# 140810_AriloTX_REV3_0_0_433MHZ_td.net
KiCad netlist of a schematic drawn in EAGLE
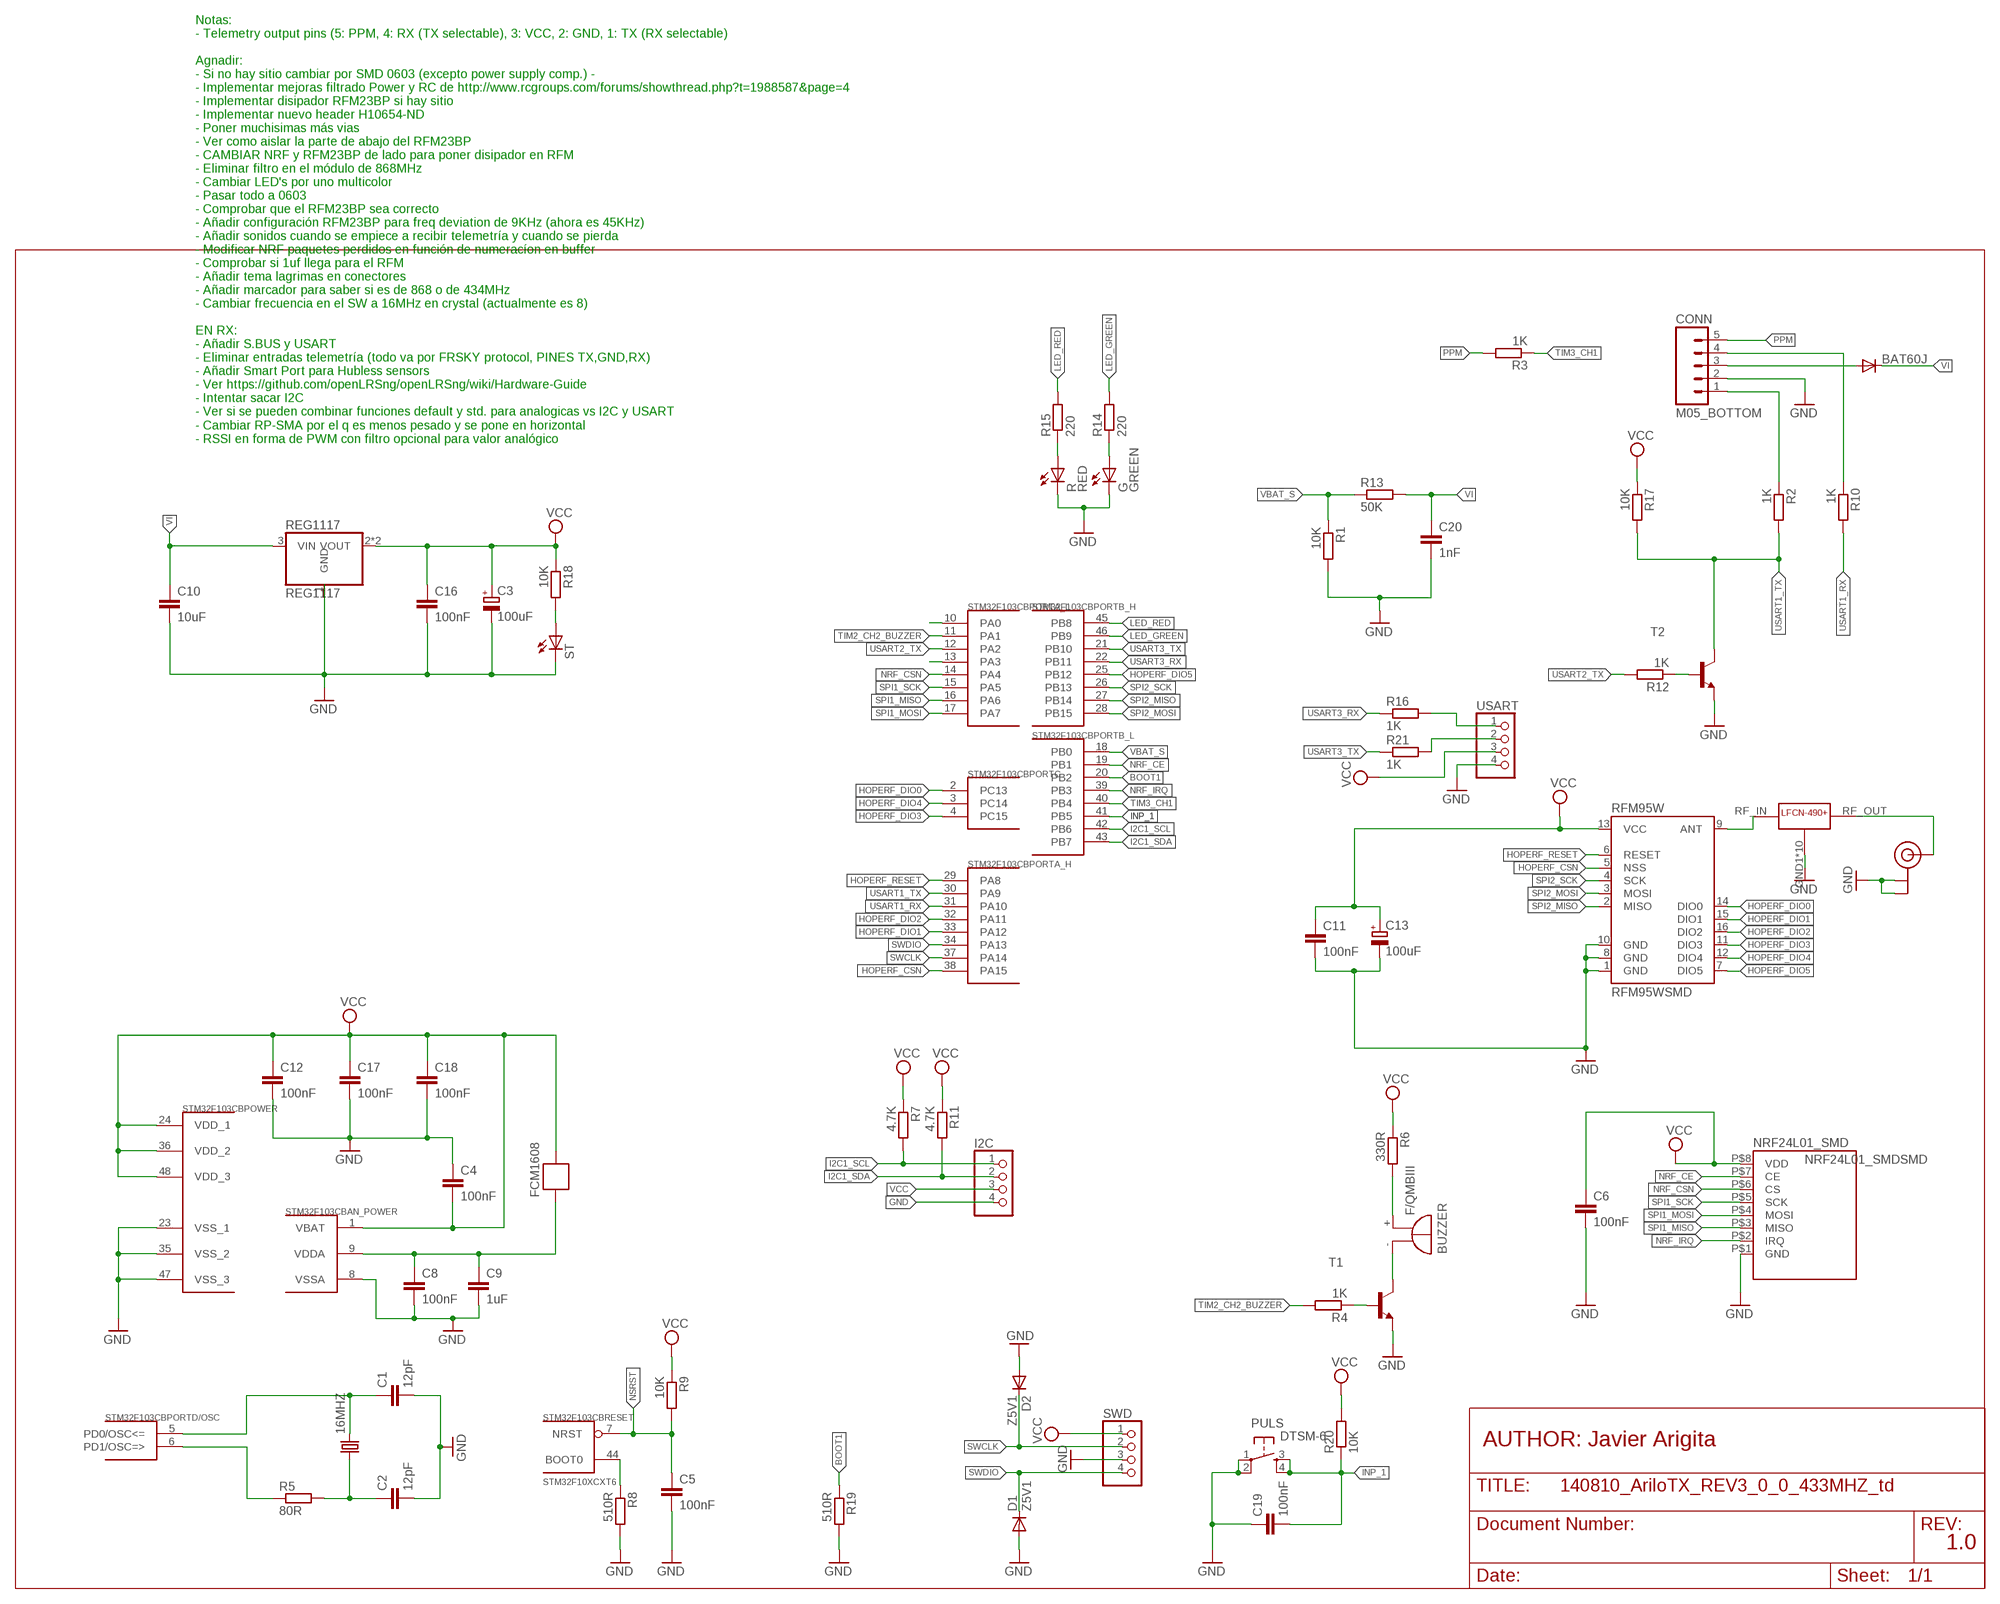
[diagram p0: schematic, sheet 1]

(export (version "E")
  (design (tool "Eeschema 10.0.6"))
  (components
    (comp (ref "16MHZ")
      (value "CRYSTAL5X3")
      (footprint "eagle-import:CRYSTAL-SMD-5X3")
      (libsource (lib "eagle-import") (part "CRYSTAL5X3"))
    )
    (comp (ref "BAT60J")
      (value "DIODE-SOD323-R")
      (footprint "eagle-import:SOD323-R")
      (libsource (lib "eagle-import") (part "DIODE-SOD323-R"))
    )
    (comp (ref "BUZZER")
      (value "F/QMBIII")
      (footprint "eagle-import:F_QMBIII")
      (libsource (lib "eagle-import") (part "F/QMBIII"))
    )
    (comp (ref "C1")
      (value "12pF")
      (footprint "eagle-import:C0603")
      (libsource (lib "eagle-import") (part "C-EUC0603"))
    )
    (comp (ref "C2")
      (value "12pF")
      (footprint "eagle-import:C0603")
      (libsource (lib "eagle-import") (part "C-EUC0603"))
    )
    (comp (ref "C3")
      (value "100uF")
      (footprint "eagle-import:SMC_B")
      (libsource (lib "eagle-import") (part "CPOL-EUSMCB"))
    )
    (comp (ref "C4")
      (value "100nF")
      (footprint "eagle-import:C0603")
      (libsource (lib "eagle-import") (part "C-EUC0603"))
    )
    (comp (ref "C5")
      (value "100nF")
      (footprint "eagle-import:C0603")
      (libsource (lib "eagle-import") (part "C-EUC0603"))
    )
    (comp (ref "C6")
      (value "100nF")
      (footprint "eagle-import:C0603")
      (libsource (lib "eagle-import") (part "C-EUC0603"))
    )
    (comp (ref "C8")
      (value "100nF")
      (footprint "eagle-import:C0603")
      (libsource (lib "eagle-import") (part "C-EUC0603"))
    )
    (comp (ref "C9")
      (value "1uF")
      (footprint "eagle-import:C0603")
      (libsource (lib "eagle-import") (part "C-EUC0603"))
    )
    (comp (ref "C10")
      (value "10uF")
      (footprint "eagle-import:C3216")
      (libsource (lib "eagle-import") (part "resistor_C-EUC3216"))
    )
    (comp (ref "C11")
      (value "100nF")
      (footprint "eagle-import:C0603")
      (libsource (lib "eagle-import") (part "C-EUC0603"))
    )
    (comp (ref "C12")
      (value "100nF")
      (footprint "eagle-import:C0603")
      (libsource (lib "eagle-import") (part "C-EUC0603"))
    )
    (comp (ref "C13")
      (value "100uF")
      (footprint "eagle-import:SMC_B")
      (libsource (lib "eagle-import") (part "CPOL-EUSMCB"))
    )
    (comp (ref "C16")
      (value "100nF")
      (footprint "eagle-import:C0603")
      (libsource (lib "eagle-import") (part "C-EUC0603"))
    )
    (comp (ref "C17")
      (value "100nF")
      (footprint "eagle-import:C0603")
      (libsource (lib "eagle-import") (part "C-EUC0603"))
    )
    (comp (ref "C18")
      (value "100nF")
      (footprint "eagle-import:C0603")
      (libsource (lib "eagle-import") (part "C-EUC0603"))
    )
    (comp (ref "C19")
      (value "100nF")
      (footprint "eagle-import:C0603")
      (libsource (lib "eagle-import") (part "C-EUC0603"))
    )
    (comp (ref "C20")
      (value "1nF")
      (footprint "eagle-import:C0603")
      (libsource (lib "eagle-import") (part "C-EUC0603"))
    )
    (comp (ref "CONN")
      (value "M05_BOTTOM")
      (footprint "eagle-import:M05_BOTTOM")
      (libsource (lib "eagle-import") (part "M05_BOTTOM"))
    )
    (comp (ref "D1")
      (value "Z5V1")
      (footprint "eagle-import:SOD323-R")
      (libsource (lib "eagle-import") (part "DIODE-SOD323-R"))
    )
    (comp (ref "D2")
      (value "Z5V1")
      (footprint "eagle-import:SOD323-R")
      (libsource (lib "eagle-import") (part "DIODE-SOD323-R"))
    )
    (comp (ref "FCM1608")
      (value "FERRITE-BEAD")
      (footprint "eagle-import:R0603")
      (libsource (lib "eagle-import") (part "FERRITE-BEAD"))
    )
    (comp (ref "G")
      (value "GREEN")
      (footprint "eagle-import:CHIP-LED0603")
      (libsource (lib "eagle-import") (part "LEDCHIP-LED0603"))
    )
    (comp (ref "I2C")
      (value "PINHD-1X4")
      (footprint "eagle-import:1X04")
      (libsource (lib "eagle-import") (part "PINHD-1X4"))
    )
    (comp (ref "LFCN490+")
      (value "LFCN490+")
      (footprint "eagle-import:LFCN490+")
      (libsource (lib "eagle-import") (part "LFCN490+"))
    )
    (comp (ref "NRF24L01_SMD")
      (value "NRF24L01_SMDSMD")
      (footprint "eagle-import:NRF24L01_SMD")
      (libsource (lib "eagle-import") (part "NRF24L01_SMDSMD"))
    )
    (comp (ref "PULS")
      (value "DTSM-6")
      (footprint "eagle-import:DTSM-6")
      (libsource (lib "eagle-import") (part "DTSM-6"))
    )
    (comp (ref "R")
      (value "RED")
      (footprint "eagle-import:CHIP-LED0603")
      (libsource (lib "eagle-import") (part "LEDCHIP-LED0603"))
    )
    (comp (ref "R1")
      (value "10K")
      (footprint "eagle-import:R0603")
      (libsource (lib "eagle-import") (part "R-EU_R0603"))
    )
    (comp (ref "R2")
      (value "1K")
      (footprint "eagle-import:R0603")
      (libsource (lib "eagle-import") (part "R-EU_R0603"))
    )
    (comp (ref "R3")
      (value "1K")
      (footprint "eagle-import:R0603")
      (libsource (lib "eagle-import") (part "R-EU_R0603"))
    )
    (comp (ref "R4")
      (value "1K")
      (footprint "eagle-import:R0603")
      (libsource (lib "eagle-import") (part "R-EU_R0603"))
    )
    (comp (ref "R5")
      (value "80R")
      (footprint "eagle-import:R0603")
      (libsource (lib "eagle-import") (part "R-EU_R0603"))
    )
    (comp (ref "R6")
      (value "330R")
      (footprint "eagle-import:R0603")
      (libsource (lib "eagle-import") (part "R-EU_R0603"))
    )
    (comp (ref "R7")
      (value "4.7K")
      (footprint "eagle-import:R0603")
      (libsource (lib "eagle-import") (part "R-EU_R0603"))
    )
    (comp (ref "R8")
      (value "510R")
      (footprint "eagle-import:R0603")
      (libsource (lib "eagle-import") (part "R-EU_R0603"))
    )
    (comp (ref "R9")
      (value "10K")
      (footprint "eagle-import:R0603")
      (libsource (lib "eagle-import") (part "R-EU_R0603"))
    )
    (comp (ref "R10")
      (value "1K")
      (footprint "eagle-import:R0603")
      (libsource (lib "eagle-import") (part "R-EU_R0603"))
    )
    (comp (ref "R11")
      (value "4.7K")
      (footprint "eagle-import:R0603")
      (libsource (lib "eagle-import") (part "R-EU_R0603"))
    )
    (comp (ref "R12")
      (value "1K")
      (footprint "eagle-import:R0603")
      (libsource (lib "eagle-import") (part "R-EU_R0603"))
    )
    (comp (ref "R13")
      (value "50K")
      (footprint "eagle-import:R0603")
      (libsource (lib "eagle-import") (part "R-EU_R0603"))
    )
    (comp (ref "R14")
      (value "220")
      (footprint "eagle-import:R0603")
      (libsource (lib "eagle-import") (part "R-EU_R0603"))
    )
    (comp (ref "R15")
      (value "220")
      (footprint "eagle-import:R0603")
      (libsource (lib "eagle-import") (part "R-EU_R0603"))
    )
    (comp (ref "R16")
      (value "1K")
      (footprint "eagle-import:R0603")
      (libsource (lib "eagle-import") (part "R-EU_R0603"))
    )
    (comp (ref "R17")
      (value "10K")
      (footprint "eagle-import:R0603")
      (libsource (lib "eagle-import") (part "R-EU_R0603"))
    )
    (comp (ref "R18")
      (value "10K")
      (footprint "eagle-import:R0603")
      (libsource (lib "eagle-import") (part "R-EU_R0603"))
    )
    (comp (ref "R19")
      (value "510R")
      (footprint "eagle-import:R0603")
      (libsource (lib "eagle-import") (part "R-EU_R0603"))
    )
    (comp (ref "R20")
      (value "10K")
      (footprint "eagle-import:R0603")
      (libsource (lib "eagle-import") (part "R-EU_R0603"))
    )
    (comp (ref "R21")
      (value "1K")
      (footprint "eagle-import:R0603")
      (libsource (lib "eagle-import") (part "R-EU_R0603"))
    )
    (comp (ref "REG1117")
      (value "REG1117")
      (footprint "eagle-import:SOT223")
      (libsource (lib "eagle-import") (part "REG1117"))
    )
    (comp (ref "RFM95W")
      (value "RFM95WSMD")
      (footprint "eagle-import:MISIEK_RFM95W_SMD")
      (libsource (lib "eagle-import") (part "MISIEK_RFM95WSMD"))
    )
    (comp (ref "ST")
      (value "LEDCHIP-LED0603")
      (footprint "eagle-import:CHIP-LED0603")
      (libsource (lib "eagle-import") (part "LEDCHIP-LED0603"))
    )
    (comp (ref "STM32F103CB")
      (value "STM32F10XCXT6")
      (footprint "eagle-import:TQFP48")
      (libsource (lib "eagle-import") (part "STM32F10XCXT6"))
    )
    (comp (ref "SWD")
      (value "PINHD-1X4")
      (footprint "eagle-import:1X04")
      (libsource (lib "eagle-import") (part "PINHD-1X4"))
    )
    (comp (ref "T1")
      (value "BC848-NPN-SOT23-BEC")
      (footprint "eagle-import:SOT23-BEC")
      (libsource (lib "eagle-import") (part "-NPN-SOT23-BECBC848"))
    )
    (comp (ref "T2")
      (value "BC848-NPN-SOT23-BEC")
      (footprint "eagle-import:SOT23-BEC")
      (libsource (lib "eagle-import") (part "-NPN-SOT23-BECBC848"))
    )
    (comp (ref "U.FL")
      (value "U.FL")
      (footprint "eagle-import:U.FL")
      (libsource (lib "eagle-import") (part "U.FL"))
    )
    (comp (ref "USART")
      (value "PINHD-1X4")
      (footprint "eagle-import:1X04")
      (libsource (lib "eagle-import") (part "PINHD-1X4"))
    )
  )
  (nets
    (net (code "1") (name "BOOT1") (class "Default")
      (node (ref "R19") (pin "1") (pinfunction "1_1") (pintype "passive"))
      (node (ref "STM32F103CB") (pin "20") (pinfunction "PB2_20") (pintype "bidirectional"))
    )
    (net (code "2") (name "GND") (class "Default")
      (node (ref "C1") (pin "2") (pinfunction "2_2") (pintype "passive"))
      (node (ref "C10") (pin "2") (pinfunction "2_2") (pintype "passive"))
      (node (ref "C11") (pin "2") (pinfunction "2_2") (pintype "passive"))
      (node (ref "C12") (pin "2") (pinfunction "2_2") (pintype "passive"))
      (node (ref "C13") (pin "-") (pinfunction "-_-") (pintype "passive"))
      (node (ref "C16") (pin "2") (pinfunction "2_2") (pintype "passive"))
      (node (ref "C17") (pin "2") (pinfunction "2_2") (pintype "passive"))
      (node (ref "C18") (pin "2") (pinfunction "2_2") (pintype "passive"))
      (node (ref "C19") (pin "1") (pinfunction "1_1") (pintype "passive"))
      (node (ref "C2") (pin "2") (pinfunction "2_2") (pintype "passive"))
      (node (ref "C20") (pin "2") (pinfunction "2_2") (pintype "passive"))
      (node (ref "C3") (pin "-") (pinfunction "-_-") (pintype "passive"))
      (node (ref "C4") (pin "1") (pinfunction "1_1") (pintype "passive"))
      (node (ref "C5") (pin "2") (pinfunction "2_2") (pintype "passive"))
      (node (ref "C6") (pin "2") (pinfunction "2_2") (pintype "passive"))
      (node (ref "C8") (pin "2") (pinfunction "2_2") (pintype "passive"))
      (node (ref "C9") (pin "2") (pinfunction "2_2") (pintype "passive"))
      (node (ref "CONN") (pin "2") (pinfunction "2_2") (pintype "passive"))
      (node (ref "D1") (pin "A") (pinfunction "A_A") (pintype "passive"))
      (node (ref "D2") (pin "A") (pinfunction "A_A") (pintype "passive"))
      (node (ref "G") (pin "C") (pinfunction "C_C") (pintype "passive"))
      (node (ref "I2C") (pin "4") (pinfunction "4_4") (pintype "passive"))
      (node (ref "LFCN490+") (pin "GND1") (pinfunction "GND_GND1") (pintype "bidirectional"))
      (node (ref "LFCN490+") (pin "GND10") (pinfunction "GND_GND10") (pintype "bidirectional"))
      (node (ref "LFCN490+") (pin "GND2") (pinfunction "GND_GND2") (pintype "bidirectional"))
      (node (ref "LFCN490+") (pin "GND3") (pinfunction "GND_GND3") (pintype "bidirectional"))
      (node (ref "LFCN490+") (pin "GND4") (pinfunction "GND_GND4") (pintype "bidirectional"))
      (node (ref "LFCN490+") (pin "GND5") (pinfunction "GND_GND5") (pintype "bidirectional"))
      (node (ref "LFCN490+") (pin "GND6") (pinfunction "GND_GND6") (pintype "bidirectional"))
      (node (ref "LFCN490+") (pin "GND7") (pinfunction "GND_GND7") (pintype "bidirectional"))
      (node (ref "LFCN490+") (pin "GND8") (pinfunction "GND_GND8") (pintype "bidirectional"))
      (node (ref "LFCN490+") (pin "GND9") (pinfunction "GND_GND9") (pintype "bidirectional"))
      (node (ref "NRF24L01_SMD") (pin "P$1") (pinfunction "GND_P$1") (pintype "power_in"))
      (node (ref "PULS") (pin "1") (pinfunction "1_1") (pintype "passive"))
      (node (ref "PULS") (pin "2") (pinfunction "2_2") (pintype "passive"))
      (node (ref "R") (pin "C") (pinfunction "C_C") (pintype "passive"))
      (node (ref "R1") (pin "2") (pinfunction "2_2") (pintype "passive"))
      (node (ref "R19") (pin "2") (pinfunction "2_2") (pintype "passive"))
      (node (ref "R8") (pin "2") (pinfunction "2_2") (pintype "passive"))
      (node (ref "REG1117") (pin "1") (pinfunction "GND_1") (pintype "power_in"))
      (node (ref "RFM95W") (pin "1") (pinfunction "GND_1") (pintype "power_in"))
      (node (ref "RFM95W") (pin "10") (pinfunction "GND_10") (pintype "power_in"))
      (node (ref "RFM95W") (pin "8") (pinfunction "GND_8") (pintype "power_in"))
      (node (ref "ST") (pin "C") (pinfunction "C_C") (pintype "passive"))
      (node (ref "STM32F103CB") (pin "23") (pinfunction "VSS_1_23") (pintype "power_in"))
      (node (ref "STM32F103CB") (pin "35") (pinfunction "VSS_2_35") (pintype "power_in"))
      (node (ref "STM32F103CB") (pin "47") (pinfunction "VSS_3_47") (pintype "power_in"))
      (node (ref "STM32F103CB") (pin "8") (pinfunction "VSSA_8") (pintype "power_in"))
      (node (ref "SWD") (pin "3") (pinfunction "3_3") (pintype "passive"))
      (node (ref "T1") (pin "E") (pinfunction "E_E") (pintype "passive"))
      (node (ref "T2") (pin "E") (pinfunction "E_E") (pintype "passive"))
      (node (ref "U.FL") (pin "P$1") (pinfunction "GND_P$1") (pintype "bidirectional"))
      (node (ref "U.FL") (pin "P$2") (pinfunction "GND_P$2") (pintype "bidirectional"))
      (node (ref "USART") (pin "4") (pinfunction "4_4") (pintype "passive"))
    )
    (net (code "3") (name "HOPERF_CSN") (class "Default")
      (node (ref "RFM95W") (pin "5") (pinfunction "NSS_5") (pintype "input"))
      (node (ref "STM32F103CB") (pin "38") (pinfunction "PA15_38") (pintype "bidirectional"))
    )
    (net (code "4") (name "HOPERF_DIO0") (class "Default")
      (node (ref "RFM95W") (pin "14") (pinfunction "DIO0_14") (pintype "input"))
      (node (ref "STM32F103CB") (pin "2") (pinfunction "PC13_2") (pintype "bidirectional"))
    )
    (net (code "5") (name "HOPERF_DIO1") (class "Default")
      (node (ref "RFM95W") (pin "15") (pinfunction "DIO1_15") (pintype "input"))
      (node (ref "STM32F103CB") (pin "33") (pinfunction "PA12_33") (pintype "bidirectional"))
    )
    (net (code "6") (name "HOPERF_DIO2") (class "Default")
      (node (ref "RFM95W") (pin "16") (pinfunction "DIO2_16") (pintype "input"))
      (node (ref "STM32F103CB") (pin "32") (pinfunction "PA11_32") (pintype "bidirectional"))
    )
    (net (code "7") (name "HOPERF_DIO3") (class "Default")
      (node (ref "RFM95W") (pin "11") (pinfunction "DIO3_11") (pintype "bidirectional"))
      (node (ref "STM32F103CB") (pin "4") (pinfunction "PC15_4") (pintype "bidirectional"))
    )
    (net (code "8") (name "HOPERF_DIO4") (class "Default")
      (node (ref "RFM95W") (pin "12") (pinfunction "DIO4_12") (pintype "bidirectional"))
      (node (ref "STM32F103CB") (pin "3") (pinfunction "PC14_3") (pintype "bidirectional"))
    )
    (net (code "9") (name "HOPERF_DIO5") (class "Default")
      (node (ref "RFM95W") (pin "7") (pinfunction "DIO5_7") (pintype "bidirectional"))
      (node (ref "STM32F103CB") (pin "25") (pinfunction "PB12_25") (pintype "bidirectional"))
    )
    (net (code "10") (name "HOPERF_RESET") (class "Default")
      (node (ref "RFM95W") (pin "6") (pinfunction "RESET_6") (pintype "output"))
      (node (ref "STM32F103CB") (pin "29") (pinfunction "PA8_29") (pintype "bidirectional"))
    )
    (net (code "11") (name "I2C1_SCL") (class "Default")
      (node (ref "I2C") (pin "1") (pinfunction "1_1") (pintype "passive"))
      (node (ref "R7") (pin "2") (pinfunction "2_2") (pintype "passive"))
      (node (ref "STM32F103CB") (pin "42") (pinfunction "PB6_42") (pintype "bidirectional"))
    )
    (net (code "12") (name "I2C1_SDA") (class "Default")
      (node (ref "I2C") (pin "2") (pinfunction "2_2") (pintype "passive"))
      (node (ref "R11") (pin "2") (pinfunction "2_2") (pintype "passive"))
      (node (ref "STM32F103CB") (pin "43") (pinfunction "PB7_43") (pintype "bidirectional"))
    )
    (net (code "13") (name "INP_1") (class "Default")
      (node (ref "C19") (pin "2") (pinfunction "2_2") (pintype "passive"))
      (node (ref "PULS") (pin "3") (pinfunction "3_3") (pintype "passive"))
      (node (ref "PULS") (pin "4") (pinfunction "4_4") (pintype "passive"))
      (node (ref "R20") (pin "1") (pinfunction "1_1") (pintype "passive"))
      (node (ref "STM32F103CB") (pin "41") (pinfunction "PB5_41") (pintype "bidirectional"))
    )
    (net (code "14") (name "LED_GREEN") (class "Default")
      (node (ref "R14") (pin "2") (pinfunction "2_2") (pintype "passive"))
      (node (ref "STM32F103CB") (pin "46") (pinfunction "PB9_46") (pintype "bidirectional"))
    )
    (net (code "15") (name "LED_RED") (class "Default")
      (node (ref "R15") (pin "2") (pinfunction "2_2") (pintype "passive"))
      (node (ref "STM32F103CB") (pin "45") (pinfunction "PB8_45") (pintype "bidirectional"))
    )
    (net (code "16") (name "NRF_CE") (class "Default")
      (node (ref "NRF24L01_SMD") (pin "P$7") (pinfunction "CE_P$7") (pintype "input"))
      (node (ref "STM32F103CB") (pin "19") (pinfunction "PB1_19") (pintype "bidirectional"))
    )
    (net (code "17") (name "NRF_CSN") (class "Default")
      (node (ref "NRF24L01_SMD") (pin "P$6") (pinfunction "CS_P$6") (pintype "input"))
      (node (ref "STM32F103CB") (pin "14") (pinfunction "PA4_14") (pintype "bidirectional"))
    )
    (net (code "18") (name "NRF_IRQ") (class "Default")
      (node (ref "NRF24L01_SMD") (pin "P$2") (pinfunction "IRQ_P$2") (pintype "output"))
      (node (ref "STM32F103CB") (pin "39") (pinfunction "PB3_39") (pintype "bidirectional"))
    )
    (net (code "19") (name "NSRST") (class "Default")
      (node (ref "C5") (pin "1") (pinfunction "1_1") (pintype "passive"))
      (node (ref "R9") (pin "2") (pinfunction "2_2") (pintype "passive"))
      (node (ref "STM32F103CB") (pin "7") (pinfunction "NRST_7") (pintype "input"))
    )
    (net (code "20") (name "Net-(16MHZ-2)") (class "Default")
      (node (ref "16MHZ") (pin "3") (pinfunction "2_3") (pintype "passive"))
      (node (ref "C1") (pin "1") (pinfunction "1_1") (pintype "passive"))
      (node (ref "STM32F103CB") (pin "5") (pinfunction "PD0/OSC<=_5") (pintype "bidirectional"))
    )
    (net (code "21") (name "Net-(16MHZ-Pad1)") (class "Default")
      (node (ref "16MHZ") (pin "1") (pinfunction "1_1") (pintype "passive"))
      (node (ref "C2") (pin "1") (pinfunction "1_1") (pintype "passive"))
      (node (ref "R5") (pin "2") (pinfunction "2_2") (pintype "passive"))
    )
    (net (code "22") (name "Net-(BAT60J-PadA)") (class "Default")
      (node (ref "BAT60J") (pin "A") (pinfunction "A_A") (pintype "passive"))
      (node (ref "CONN") (pin "3") (pinfunction "3_3") (pintype "passive"))
    )
    (net (code "23") (name "Net-(BUZZER-+)") (class "Default")
      (node (ref "BUZZER") (pin "-") (pinfunction "+_-") (pintype "passive"))
      (node (ref "T1") (pin "C") (pinfunction "C_C") (pintype "passive"))
    )
    (net (code "24") (name "Net-(BUZZER--)") (class "Default")
      (node (ref "BUZZER") (pin "+") (pinfunction "-_+") (pintype "passive"))
      (node (ref "R6") (pin "2") (pinfunction "2_2") (pintype "passive"))
    )
    (net (code "25") (name "Net-(CONN-Pad1)") (class "Default")
      (node (ref "CONN") (pin "1") (pinfunction "1_1") (pintype "passive"))
      (node (ref "R2") (pin "1") (pinfunction "1_1") (pintype "passive"))
    )
    (net (code "26") (name "Net-(CONN-Pad4)") (class "Default")
      (node (ref "CONN") (pin "4") (pinfunction "4_4") (pintype "passive"))
      (node (ref "R10") (pin "1") (pinfunction "1_1") (pintype "passive"))
    )
    (net (code "27") (name "Net-(FCM1608-P$2)") (class "Default")
      (node (ref "C8") (pin "1") (pinfunction "1_1") (pintype "passive"))
      (node (ref "C9") (pin "1") (pinfunction "1_1") (pintype "passive"))
      (node (ref "FCM1608") (pin "2") (pinfunction "P$2_2") (pintype "bidirectional"))
      (node (ref "STM32F103CB") (pin "9") (pinfunction "VDDA_9") (pintype "power_in"))
    )
    (net (code "28") (name "Net-(G-PadA)") (class "Default")
      (node (ref "G") (pin "A") (pinfunction "A_A") (pintype "passive"))
      (node (ref "R14") (pin "1") (pinfunction "1_1") (pintype "passive"))
    )
    (net (code "29") (name "Net-(LFCN490+-RF_INP)") (class "Default")
      (node (ref "LFCN490+") (pin "RF_IN") (pinfunction "RF_INP_RF_IN") (pintype "bidirectional"))
      (node (ref "RFM95W") (pin "9") (pinfunction "ANT_9") (pintype "bidirectional"))
    )
    (net (code "30") (name "Net-(LFCN490+-RF_OUTP)") (class "Default")
      (node (ref "LFCN490+") (pin "RF_OUT") (pinfunction "RF_OUTP_RF_OUT") (pintype "bidirectional"))
      (node (ref "U.FL") (pin "P$3") (pinfunction "SIGNAL_P$3") (pintype "bidirectional"))
    )
    (net (code "31") (name "Net-(R-PadA)") (class "Default")
      (node (ref "R") (pin "A") (pinfunction "A_A") (pintype "passive"))
      (node (ref "R15") (pin "1") (pinfunction "1_1") (pintype "passive"))
    )
    (net (code "32") (name "Net-(R4-Pad1)") (class "Default")
      (node (ref "R4") (pin "1") (pinfunction "1_1") (pintype "passive"))
      (node (ref "T1") (pin "B") (pinfunction "B_B") (pintype "passive"))
    )
    (net (code "33") (name "Net-(R12-Pad1)") (class "Default")
      (node (ref "R12") (pin "1") (pinfunction "1_1") (pintype "passive"))
      (node (ref "T2") (pin "B") (pinfunction "B_B") (pintype "passive"))
    )
    (net (code "34") (name "Net-(R16-Pad2)") (class "Default")
      (node (ref "R16") (pin "2") (pinfunction "2_2") (pintype "passive"))
      (node (ref "USART") (pin "1") (pinfunction "1_1") (pintype "passive"))
    )
    (net (code "35") (name "Net-(R18-Pad2)") (class "Default")
      (node (ref "R18") (pin "2") (pinfunction "2_2") (pintype "passive"))
      (node (ref "ST") (pin "A") (pinfunction "A_A") (pintype "passive"))
    )
    (net (code "36") (name "Net-(R21-Pad2)") (class "Default")
      (node (ref "R21") (pin "2") (pinfunction "2_2") (pintype "passive"))
      (node (ref "USART") (pin "2") (pinfunction "2_2") (pintype "passive"))
    )
    (net (code "37") (name "Net-(STM32F103CBG-PD1{slash}OSC=>)") (class "Default")
      (node (ref "R5") (pin "1") (pinfunction "1_1") (pintype "passive"))
      (node (ref "STM32F103CB") (pin "6") (pinfunction "PD1/OSC=>_6") (pintype "bidirectional"))
    )
    (net (code "38") (name "Net-(STM32F103CBI-BOOT0)") (class "Default")
      (node (ref "R8") (pin "1") (pinfunction "1_1") (pintype "passive"))
      (node (ref "STM32F103CB") (pin "44") (pinfunction "BOOT0_44") (pintype "input"))
    )
    (net (code "39") (name "PPM") (class "Default")
      (node (ref "CONN") (pin "5") (pinfunction "5_5") (pintype "passive"))
      (node (ref "R3") (pin "2") (pinfunction "2_2") (pintype "passive"))
    )
    (net (code "40") (name "SPI1_MISO") (class "Default")
      (node (ref "NRF24L01_SMD") (pin "P$3") (pinfunction "MISO_P$3") (pintype "output"))
      (node (ref "STM32F103CB") (pin "16") (pinfunction "PA6_16") (pintype "bidirectional"))
    )
    (net (code "41") (name "SPI1_MOSI") (class "Default")
      (node (ref "NRF24L01_SMD") (pin "P$4") (pinfunction "MOSI_P$4") (pintype "input"))
      (node (ref "STM32F103CB") (pin "17") (pinfunction "PA7_17") (pintype "bidirectional"))
    )
    (net (code "42") (name "SPI1_SCK") (class "Default")
      (node (ref "NRF24L01_SMD") (pin "P$5") (pinfunction "SCK_P$5") (pintype "input"))
      (node (ref "STM32F103CB") (pin "15") (pinfunction "PA5_15") (pintype "bidirectional"))
    )
    (net (code "43") (name "SPI2_MISO") (class "Default")
      (node (ref "RFM95W") (pin "2") (pinfunction "MISO_2") (pintype "output"))
      (node (ref "STM32F103CB") (pin "27") (pinfunction "PB14_27") (pintype "bidirectional"))
    )
    (net (code "44") (name "SPI2_MOSI") (class "Default")
      (node (ref "RFM95W") (pin "3") (pinfunction "MOSI_3") (pintype "input"))
      (node (ref "STM32F103CB") (pin "28") (pinfunction "PB15_28") (pintype "bidirectional"))
    )
    (net (code "45") (name "SPI2_SCK") (class "Default")
      (node (ref "RFM95W") (pin "4") (pinfunction "SCK_4") (pintype "input"))
      (node (ref "STM32F103CB") (pin "26") (pinfunction "PB13_26") (pintype "bidirectional"))
    )
    (net (code "46") (name "SWCLK") (class "Default")
      (node (ref "D2") (pin "C") (pinfunction "C_C") (pintype "passive"))
      (node (ref "STM32F103CB") (pin "37") (pinfunction "PA14_37") (pintype "bidirectional"))
      (node (ref "SWD") (pin "2") (pinfunction "2_2") (pintype "passive"))
    )
    (net (code "47") (name "SWDIO") (class "Default")
      (node (ref "D1") (pin "C") (pinfunction "C_C") (pintype "passive"))
      (node (ref "STM32F103CB") (pin "34") (pinfunction "PA13_34") (pintype "bidirectional"))
      (node (ref "SWD") (pin "4") (pinfunction "4_4") (pintype "passive"))
    )
    (net (code "48") (name "TIM2_CH2_BUZZER") (class "Default")
      (node (ref "R4") (pin "2") (pinfunction "2_2") (pintype "passive"))
      (node (ref "STM32F103CB") (pin "11") (pinfunction "PA1_11") (pintype "bidirectional"))
    )
    (net (code "49") (name "TIM3_CH1") (class "Default")
      (node (ref "R3") (pin "1") (pinfunction "1_1") (pintype "passive"))
      (node (ref "STM32F103CB") (pin "40") (pinfunction "PB4_40") (pintype "bidirectional"))
    )
    (net (code "50") (name "USART1_RX") (class "Default")
      (node (ref "R10") (pin "2") (pinfunction "2_2") (pintype "passive"))
      (node (ref "STM32F103CB") (pin "31") (pinfunction "PA10_31") (pintype "bidirectional"))
    )
    (net (code "51") (name "USART1_TX") (class "Default")
      (node (ref "R17") (pin "2") (pinfunction "2_2") (pintype "passive"))
      (node (ref "R2") (pin "2") (pinfunction "2_2") (pintype "passive"))
      (node (ref "STM32F103CB") (pin "30") (pinfunction "PA9_30") (pintype "bidirectional"))
      (node (ref "T2") (pin "C") (pinfunction "C_C") (pintype "passive"))
    )
    (net (code "52") (name "USART2_TX") (class "Default")
      (node (ref "R12") (pin "2") (pinfunction "2_2") (pintype "passive"))
      (node (ref "STM32F103CB") (pin "12") (pinfunction "PA2_12") (pintype "bidirectional"))
    )
    (net (code "53") (name "USART3_RX") (class "Default")
      (node (ref "R16") (pin "1") (pinfunction "1_1") (pintype "passive"))
      (node (ref "STM32F103CB") (pin "22") (pinfunction "PB11_22") (pintype "bidirectional"))
    )
    (net (code "54") (name "USART3_TX") (class "Default")
      (node (ref "R21") (pin "1") (pinfunction "1_1") (pintype "passive"))
      (node (ref "STM32F103CB") (pin "21") (pinfunction "PB10_21") (pintype "bidirectional"))
    )
    (net (code "55") (name "VBAT_S") (class "Default")
      (node (ref "R1") (pin "1") (pinfunction "1_1") (pintype "passive"))
      (node (ref "R13") (pin "1") (pinfunction "1_1") (pintype "passive"))
      (node (ref "STM32F103CB") (pin "18") (pinfunction "PB0_18") (pintype "bidirectional"))
    )
    (net (code "56") (name "VCC") (class "Default")
      (node (ref "C11") (pin "1") (pinfunction "1_1") (pintype "passive"))
      (node (ref "C12") (pin "1") (pinfunction "1_1") (pintype "passive"))
      (node (ref "C13") (pin "+") (pinfunction "+_+") (pintype "passive"))
      (node (ref "C16") (pin "1") (pinfunction "1_1") (pintype "passive"))
      (node (ref "C17") (pin "1") (pinfunction "1_1") (pintype "passive"))
      (node (ref "C18") (pin "1") (pinfunction "1_1") (pintype "passive"))
      (node (ref "C3") (pin "+") (pinfunction "+_+") (pintype "passive"))
      (node (ref "C4") (pin "2") (pinfunction "2_2") (pintype "passive"))
      (node (ref "C6") (pin "1") (pinfunction "1_1") (pintype "passive"))
      (node (ref "FCM1608") (pin "1") (pinfunction "P$1_1") (pintype "bidirectional"))
      (node (ref "I2C") (pin "3") (pinfunction "3_3") (pintype "passive"))
      (node (ref "NRF24L01_SMD") (pin "P$8") (pinfunction "VDD_P$8") (pintype "bidirectional"))
      (node (ref "R11") (pin "1") (pinfunction "1_1") (pintype "passive"))
      (node (ref "R17") (pin "1") (pinfunction "1_1") (pintype "passive"))
      (node (ref "R18") (pin "1") (pinfunction "1_1") (pintype "passive"))
      (node (ref "R20") (pin "2") (pinfunction "2_2") (pintype "passive"))
      (node (ref "R6") (pin "1") (pinfunction "1_1") (pintype "passive"))
      (node (ref "R7") (pin "1") (pinfunction "1_1") (pintype "passive"))
      (node (ref "R9") (pin "1") (pinfunction "1_1") (pintype "passive"))
      (node (ref "REG1117") (pin "2") (pinfunction "VOUT_2") (pintype "power_in"))
      (node (ref "REG1117") (pin "4") (pinfunction "VOUT_4") (pintype "power_in"))
      (node (ref "RFM95W") (pin "13") (pinfunction "VCC_13") (pintype "bidirectional"))
      (node (ref "STM32F103CB") (pin "1") (pinfunction "VBAT_1") (pintype "power_in"))
      (node (ref "STM32F103CB") (pin "24") (pinfunction "VDD_1_24") (pintype "power_in"))
      (node (ref "STM32F103CB") (pin "36") (pinfunction "VDD_2_36") (pintype "power_in"))
      (node (ref "STM32F103CB") (pin "48") (pinfunction "VDD_3_48") (pintype "power_in"))
      (node (ref "SWD") (pin "1") (pinfunction "1_1") (pintype "passive"))
      (node (ref "USART") (pin "3") (pinfunction "3_3") (pintype "passive"))
    )
    (net (code "57") (name "VI") (class "Default")
      (node (ref "BAT60J") (pin "C") (pinfunction "C_C") (pintype "passive"))
      (node (ref "C10") (pin "1") (pinfunction "1_1") (pintype "passive"))
      (node (ref "C20") (pin "1") (pinfunction "1_1") (pintype "passive"))
      (node (ref "R13") (pin "2") (pinfunction "2_2") (pintype "passive"))
      (node (ref "REG1117") (pin "3") (pinfunction "VIN_3") (pintype "input"))
    )
    (net (code "58") (name "unconnected-(STM32F103CBC-PA0-Pad10)") (class "Default")
      (node (ref "STM32F103CB") (pin "10") (pinfunction "PA0_10") (pintype "bidirectional"))
    )
    (net (code "59") (name "unconnected-(STM32F103CBC-PA3-Pad13)") (class "Default")
      (node (ref "STM32F103CB") (pin "13") (pinfunction "PA3_13") (pintype "bidirectional"))
    )
  )
)
